# schematic_rack-monitor.net
KiCad netlist of a schematic drawn in EasyEDA
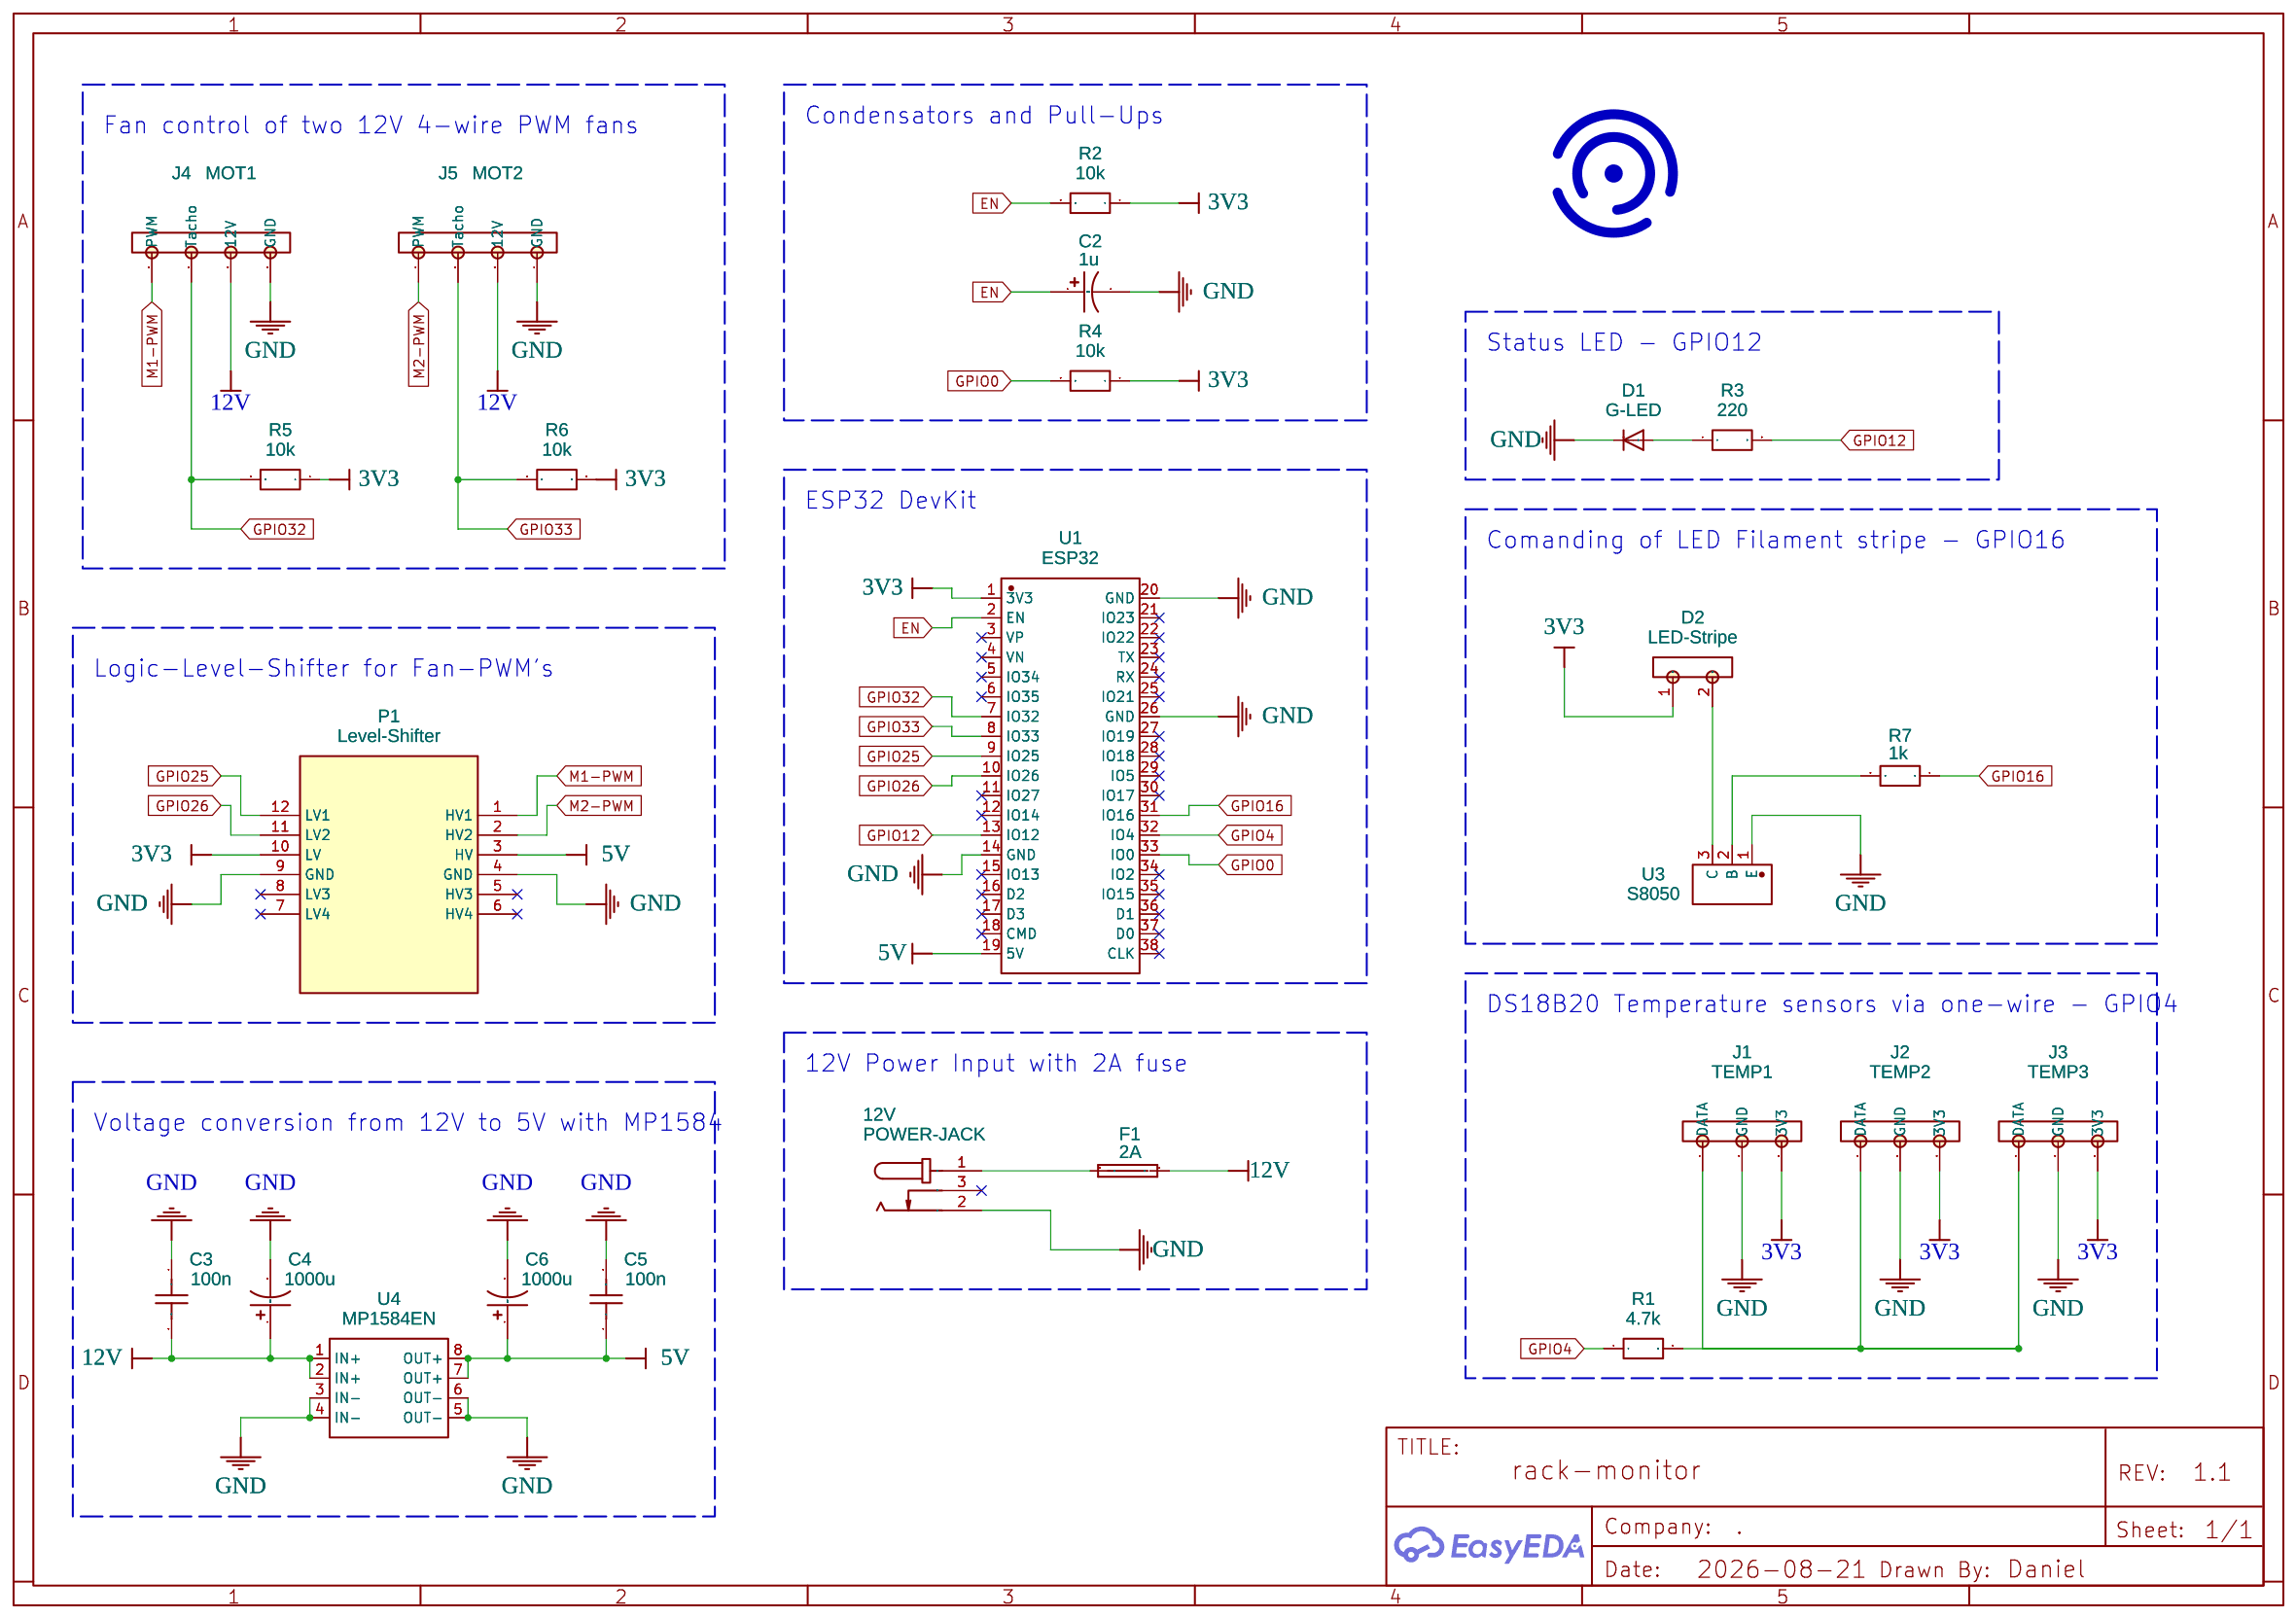
[diagram p0: schematic sheet]

(export (version "E")
  (design (tool "Eeschema 10.0.6"))
  (components
    (comp (ref "12V")
      (value "POWER-JACK")
      (fields (field (name "Manufacturer") "索峰"))
      (libsource (lib "") (part "POWER-JACK"))
    )
    (comp (ref "C2") (value "1u") (libsource (lib "") (part "C_Tan_SMD_A_US_1")))
    (comp (ref "C3") (value "100n") (libsource (lib "") (part "C_0603_US_1")))
    (comp (ref "C4") (value "1000u") (libsource (lib "") (part "C_Tan_SMD_A_US")))
    (comp (ref "C5") (value "100n") (libsource (lib "") (part "C_0603_US")))
    (comp (ref "C6") (value "1000u") (libsource (lib "") (part "C_Tan_SMD_A_US")))
    (comp (ref "D1") (value "G-LED") (libsource (lib "") (part "DIODE")))
    (comp (ref "D2") (value "LED-Stripe") (libsource (lib "") (part "CON1X02 COPY")))
    (comp (ref "F1") (value "2A") (libsource (lib "") (part "FUSE HOLDER WITH COVER FOR 5X20MM FUSE")))
    (comp (ref "J1") (value "TEMP1") (libsource (lib "") (part "CON1X03")))
    (comp (ref "J2") (value "TEMP2") (libsource (lib "") (part "CON1X03")))
    (comp (ref "J3") (value "TEMP3") (libsource (lib "") (part "CON1X03")))
    (comp (ref "J4") (value "MOT1") (libsource (lib "") (part "CON1X04")))
    (comp (ref "J5") (value "MOT2") (libsource (lib "") (part "CON1X04")))
    (comp (ref "P1") (value "Level-Shifter") (libsource (lib "") (part "Logic_Level Bidirectional")))
    (comp (ref "R1") (value "4.7k") (libsource (lib "") (part "R_0603_EU_1")))
    (comp (ref "R2") (value "10k") (libsource (lib "") (part "R_0603_EU")))
    (comp (ref "R3") (value "220") (libsource (lib "") (part "R_0603_EU_1")))
    (comp (ref "R4") (value "10k") (libsource (lib "") (part "R_0603_EU")))
    (comp (ref "R5") (value "10k") (libsource (lib "") (part "R_0603_EU")))
    (comp (ref "R6") (value "10k") (libsource (lib "") (part "R_0603_EU_1")))
    (comp (ref "R7") (value "1k") (libsource (lib "") (part "R_0603_EU")))
    (comp (ref "U1")
      (value "ESP32")
      (fields
        (field (name "Manufacturer Part") "ESP32-DEVKITC-VE")
        (field (name "Manufacturer") "ESPRESSIF(乐鑫)")
      )
      (libsource (lib "") (part "ESP32-DEVKITC-VE"))
    )
    (comp (ref "U3")
      (value "S8050")
      (fields (field (name "Manufacturer Part") "SS8050D331") (field (name "Manufacturer") "ALJ(龙晶微)"))
      (libsource (lib "") (part "SS8050D331"))
    )
    (comp (ref "U4")
      (value "MP1584EN")
      (fields (field (name "Manufacturer Part") "MP1584EN_moudle"))
      (libsource (lib "") (part "MP1584EN_MOUDLE"))
    )
  )
  (nets
    (net (code "1") (name "3V3") (class "Default")
      (node (ref "D2") (pin "1") (pinfunction "3V_1") (pintype "unspecified"))
      (node (ref "J1") (pin "3") (pinfunction "3V3_3") (pintype "unspecified"))
      (node (ref "J2") (pin "3") (pinfunction "3V3_3") (pintype "unspecified"))
      (node (ref "J3") (pin "3") (pinfunction "3V3_3") (pintype "unspecified"))
      (node (ref "P1") (pin "10") (pinfunction "LV_10") (pintype "unspecified"))
      (node (ref "R2") (pin "1") (pinfunction "1_1") (pintype "unspecified"))
      (node (ref "R4") (pin "1") (pinfunction "1_1") (pintype "unspecified"))
      (node (ref "R5") (pin "1") (pinfunction "1_1") (pintype "unspecified"))
      (node (ref "R6") (pin "2") (pinfunction "2_2") (pintype "unspecified"))
      (node (ref "U1") (pin "1") (pinfunction "3V3_1") (pintype "unspecified"))
    )
    (net (code "2") (name "5V") (class "Default")
      (node (ref "C5") (pin "1") (pinfunction "1_1") (pintype "unspecified"))
      (node (ref "C6") (pin "1") (pinfunction "1_1") (pintype "unspecified"))
      (node (ref "P1") (pin "3") (pinfunction "HV_3") (pintype "unspecified"))
      (node (ref "U1") (pin "19") (pinfunction "5V_19") (pintype "unspecified"))
      (node (ref "U4") (pin "7") (pinfunction "OUT+_7") (pintype "unspecified"))
      (node (ref "U4") (pin "8") (pinfunction "OUT+_8") (pintype "unspecified"))
    )
    (net (code "3") (name "12V") (class "Default")
      (node (ref "C3") (pin "2") (pinfunction "2_2") (pintype "unspecified"))
      (node (ref "C4") (pin "1") (pinfunction "1_1") (pintype "unspecified"))
      (node (ref "F1") (pin "2") (pinfunction "2_2") (pintype "unspecified"))
      (node (ref "J4") (pin "3") (pinfunction "12V_3") (pintype "unspecified"))
      (node (ref "J5") (pin "3") (pinfunction "12V_3") (pintype "unspecified"))
      (node (ref "U4") (pin "1") (pinfunction "IN+_1") (pintype "unspecified"))
      (node (ref "U4") (pin "2") (pinfunction "IN+_2") (pintype "unspecified"))
    )
    (net (code "4") (name "EN") (class "Default")
      (node (ref "C2") (pin "1") (pinfunction "1_1") (pintype "unspecified"))
      (node (ref "R2") (pin "2") (pinfunction "2_2") (pintype "unspecified"))
      (node (ref "U1") (pin "2") (pinfunction "EN_2") (pintype "unspecified"))
    )
    (net (code "5") (name "GND") (class "Default")
      (node (ref "12V") (pin "2") (pinfunction "2_2") (pintype "unspecified"))
      (node (ref "C2") (pin "2") (pinfunction "2_2") (pintype "unspecified"))
      (node (ref "C3") (pin "1") (pinfunction "1_1") (pintype "unspecified"))
      (node (ref "C4") (pin "2") (pinfunction "2_2") (pintype "unspecified"))
      (node (ref "C5") (pin "2") (pinfunction "2_2") (pintype "unspecified"))
      (node (ref "C6") (pin "2") (pinfunction "2_2") (pintype "unspecified"))
      (node (ref "D1") (pin "2") (pinfunction "2_2") (pintype "unspecified"))
      (node (ref "J1") (pin "2") (pinfunction "GND_2") (pintype "unspecified"))
      (node (ref "J2") (pin "2") (pinfunction "GND_2") (pintype "unspecified"))
      (node (ref "J3") (pin "2") (pinfunction "GND_2") (pintype "unspecified"))
      (node (ref "J4") (pin "4") (pinfunction "GND_4") (pintype "unspecified"))
      (node (ref "J5") (pin "4") (pinfunction "GND_4") (pintype "unspecified"))
      (node (ref "P1") (pin "4") (pinfunction "GND_4") (pintype "unspecified"))
      (node (ref "P1") (pin "9") (pinfunction "GND_9") (pintype "unspecified"))
      (node (ref "U1") (pin "14") (pinfunction "GND_14") (pintype "unspecified"))
      (node (ref "U1") (pin "20") (pinfunction "GND_20") (pintype "unspecified"))
      (node (ref "U1") (pin "26") (pinfunction "GND_26") (pintype "unspecified"))
      (node (ref "U3") (pin "1") (pinfunction "E_1") (pintype "unspecified"))
      (node (ref "U4") (pin "3") (pinfunction "IN-_3") (pintype "unspecified"))
      (node (ref "U4") (pin "4") (pinfunction "IN-_4") (pintype "unspecified"))
      (node (ref "U4") (pin "5") (pinfunction "OUT-_5") (pintype "unspecified"))
      (node (ref "U4") (pin "6") (pinfunction "OUT-_6") (pintype "unspecified"))
    )
    (net (code "6") (name "GPIO0") (class "Default")
      (node (ref "R4") (pin "2") (pinfunction "2_2") (pintype "unspecified"))
      (node (ref "U1") (pin "33") (pinfunction "IO0_33") (pintype "unspecified"))
    )
    (net (code "7") (name "GPIO4") (class "Default")
      (node (ref "R1") (pin "1") (pinfunction "1_1") (pintype "unspecified"))
      (node (ref "U1") (pin "32") (pinfunction "IO4_32") (pintype "unspecified"))
    )
    (net (code "8") (name "GPIO12") (class "Default")
      (node (ref "R3") (pin "2") (pinfunction "2_2") (pintype "unspecified"))
      (node (ref "U1") (pin "13") (pinfunction "IO12_13") (pintype "unspecified"))
    )
    (net (code "9") (name "GPIO16") (class "Default")
      (node (ref "R7") (pin "1") (pinfunction "1_1") (pintype "unspecified"))
      (node (ref "U1") (pin "31") (pinfunction "IO16_31") (pintype "unspecified"))
    )
    (net (code "10") (name "GPIO25") (class "Default")
      (node (ref "P1") (pin "12") (pinfunction "LV1_12") (pintype "unspecified"))
      (node (ref "U1") (pin "9") (pinfunction "IO25_9") (pintype "unspecified"))
    )
    (net (code "11") (name "GPIO26") (class "Default")
      (node (ref "P1") (pin "11") (pinfunction "LV2_11") (pintype "unspecified"))
      (node (ref "U1") (pin "10") (pinfunction "IO26_10") (pintype "unspecified"))
    )
    (net (code "12") (name "GPIO32") (class "Default")
      (node (ref "J4") (pin "2") (pinfunction "Tacho_2") (pintype "unspecified"))
      (node (ref "R5") (pin "2") (pinfunction "2_2") (pintype "unspecified"))
      (node (ref "U1") (pin "7") (pinfunction "IO32_7") (pintype "unspecified"))
    )
    (net (code "13") (name "GPIO33") (class "Default")
      (node (ref "J5") (pin "2") (pinfunction "Tacho_2") (pintype "unspecified"))
      (node (ref "R6") (pin "1") (pinfunction "1_1") (pintype "unspecified"))
      (node (ref "U1") (pin "8") (pinfunction "IO33_8") (pintype "unspecified"))
    )
    (net (code "14") (name "M1-PWM") (class "Default")
      (node (ref "J4") (pin "1") (pinfunction "PWM_1") (pintype "unspecified"))
      (node (ref "P1") (pin "1") (pinfunction "HV1_1") (pintype "unspecified"))
    )
    (net (code "15") (name "M2-PWM") (class "Default")
      (node (ref "J5") (pin "1") (pinfunction "PWM_1") (pintype "unspecified"))
      (node (ref "P1") (pin "2") (pinfunction "HV2_2") (pintype "unspecified"))
    )
    (net (code "16") (name "Net-(12V-Pad1)") (class "Default")
      (node (ref "12V") (pin "1") (pinfunction "1_1") (pintype "unspecified"))
      (node (ref "F1") (pin "1") (pinfunction "1_1") (pintype "unspecified"))
    )
    (net (code "17") (name "Net-(D1-Pad1)") (class "Default")
      (node (ref "D1") (pin "1") (pinfunction "1_1") (pintype "unspecified"))
      (node (ref "R3") (pin "1") (pinfunction "1_1") (pintype "unspecified"))
    )
    (net (code "18") (name "Net-(D2-GND)") (class "Default")
      (node (ref "D2") (pin "2") (pinfunction "GND_2") (pintype "unspecified"))
      (node (ref "U3") (pin "3") (pinfunction "C_3") (pintype "unspecified"))
    )
    (net (code "19") (name "Net-(J1-DATA)") (class "Default")
      (node (ref "J1") (pin "1") (pinfunction "DATA_1") (pintype "unspecified"))
      (node (ref "J2") (pin "1") (pinfunction "DATA_1") (pintype "unspecified"))
      (node (ref "J3") (pin "1") (pinfunction "DATA_1") (pintype "unspecified"))
      (node (ref "R1") (pin "2") (pinfunction "2_2") (pintype "unspecified"))
    )
    (net (code "20") (name "Net-(U3-B)") (class "Default")
      (node (ref "R7") (pin "2") (pinfunction "2_2") (pintype "unspecified"))
      (node (ref "U3") (pin "2") (pinfunction "B_2") (pintype "unspecified"))
    )
    (net (code "21") (name "unconnected-(12V-Pad3)") (class "Default")
      (node (ref "12V") (pin "3") (pinfunction "3_3") (pintype "unspecified+no_connect"))
    )
    (net (code "22") (name "unconnected-(P1-HV3-Pad5)") (class "Default")
      (node (ref "P1") (pin "5") (pinfunction "HV3_5") (pintype "unspecified+no_connect"))
    )
    (net (code "23") (name "unconnected-(P1-HV4-Pad6)") (class "Default")
      (node (ref "P1") (pin "6") (pinfunction "HV4_6") (pintype "unspecified+no_connect"))
    )
    (net (code "24") (name "unconnected-(P1-LV3-Pad8)") (class "Default")
      (node (ref "P1") (pin "8") (pinfunction "LV3_8") (pintype "unspecified+no_connect"))
    )
    (net (code "25") (name "unconnected-(P1-LV4-Pad7)") (class "Default")
      (node (ref "P1") (pin "7") (pinfunction "LV4_7") (pintype "unspecified+no_connect"))
    )
    (net (code "26") (name "unconnected-(U1-CLK-Pad38)") (class "Default")
      (node (ref "U1") (pin "38") (pinfunction "CLK_38") (pintype "unspecified+no_connect"))
    )
    (net (code "27") (name "unconnected-(U1-CMD-Pad18)") (class "Default")
      (node (ref "U1") (pin "18") (pinfunction "CMD_18") (pintype "unspecified+no_connect"))
    )
    (net (code "28") (name "unconnected-(U1-D0-Pad37)") (class "Default")
      (node (ref "U1") (pin "37") (pinfunction "D0_37") (pintype "unspecified+no_connect"))
    )
    (net (code "29") (name "unconnected-(U1-D1-Pad36)") (class "Default")
      (node (ref "U1") (pin "36") (pinfunction "D1_36") (pintype "unspecified+no_connect"))
    )
    (net (code "30") (name "unconnected-(U1-D2-Pad16)") (class "Default")
      (node (ref "U1") (pin "16") (pinfunction "D2_16") (pintype "unspecified+no_connect"))
    )
    (net (code "31") (name "unconnected-(U1-D3-Pad17)") (class "Default")
      (node (ref "U1") (pin "17") (pinfunction "D3_17") (pintype "unspecified+no_connect"))
    )
    (net (code "32") (name "unconnected-(U1-IO2-Pad34)") (class "Default")
      (node (ref "U1") (pin "34") (pinfunction "IO2_34") (pintype "unspecified+no_connect"))
    )
    (net (code "33") (name "unconnected-(U1-IO5-Pad29)") (class "Default")
      (node (ref "U1") (pin "29") (pinfunction "IO5_29") (pintype "unspecified+no_connect"))
    )
    (net (code "34") (name "unconnected-(U1-IO13-Pad15)") (class "Default")
      (node (ref "U1") (pin "15") (pinfunction "IO13_15") (pintype "unspecified+no_connect"))
    )
    (net (code "35") (name "unconnected-(U1-IO14-Pad12)") (class "Default")
      (node (ref "U1") (pin "12") (pinfunction "IO14_12") (pintype "unspecified+no_connect"))
    )
    (net (code "36") (name "unconnected-(U1-IO15-Pad35)") (class "Default")
      (node (ref "U1") (pin "35") (pinfunction "IO15_35") (pintype "unspecified+no_connect"))
    )
    (net (code "37") (name "unconnected-(U1-IO17-Pad30)") (class "Default")
      (node (ref "U1") (pin "30") (pinfunction "IO17_30") (pintype "unspecified+no_connect"))
    )
    (net (code "38") (name "unconnected-(U1-IO18-Pad28)") (class "Default")
      (node (ref "U1") (pin "28") (pinfunction "IO18_28") (pintype "unspecified+no_connect"))
    )
    (net (code "39") (name "unconnected-(U1-IO19-Pad27)") (class "Default")
      (node (ref "U1") (pin "27") (pinfunction "IO19_27") (pintype "unspecified+no_connect"))
    )
    (net (code "40") (name "unconnected-(U1-IO21-Pad25)") (class "Default")
      (node (ref "U1") (pin "25") (pinfunction "IO21_25") (pintype "unspecified+no_connect"))
    )
    (net (code "41") (name "unconnected-(U1-IO22-Pad22)") (class "Default")
      (node (ref "U1") (pin "22") (pinfunction "IO22_22") (pintype "unspecified+no_connect"))
    )
    (net (code "42") (name "unconnected-(U1-IO23-Pad21)") (class "Default")
      (node (ref "U1") (pin "21") (pinfunction "IO23_21") (pintype "unspecified+no_connect"))
    )
    (net (code "43") (name "unconnected-(U1-IO27-Pad11)") (class "Default")
      (node (ref "U1") (pin "11") (pinfunction "IO27_11") (pintype "unspecified+no_connect"))
    )
    (net (code "44") (name "unconnected-(U1-IO34-Pad5)") (class "Default")
      (node (ref "U1") (pin "5") (pinfunction "IO34_5") (pintype "unspecified+no_connect"))
    )
    (net (code "45") (name "unconnected-(U1-IO35-Pad6)") (class "Default")
      (node (ref "U1") (pin "6") (pinfunction "IO35_6") (pintype "unspecified+no_connect"))
    )
    (net (code "46") (name "unconnected-(U1-RX-Pad24)") (class "Default")
      (node (ref "U1") (pin "24") (pinfunction "RX_24") (pintype "unspecified+no_connect"))
    )
    (net (code "47") (name "unconnected-(U1-TX-Pad23)") (class "Default")
      (node (ref "U1") (pin "23") (pinfunction "TX_23") (pintype "unspecified+no_connect"))
    )
    (net (code "48") (name "unconnected-(U1-VN-Pad4)") (class "Default")
      (node (ref "U1") (pin "4") (pinfunction "VN_4") (pintype "unspecified+no_connect"))
    )
    (net (code "49") (name "unconnected-(U1-VP-Pad3)") (class "Default")
      (node (ref "U1") (pin "3") (pinfunction "VP_3") (pintype "unspecified+no_connect"))
    )
  )
)
